# OnOnfre_DevBoard.net
KiCad netlist of a schematic drawn in EAGLE
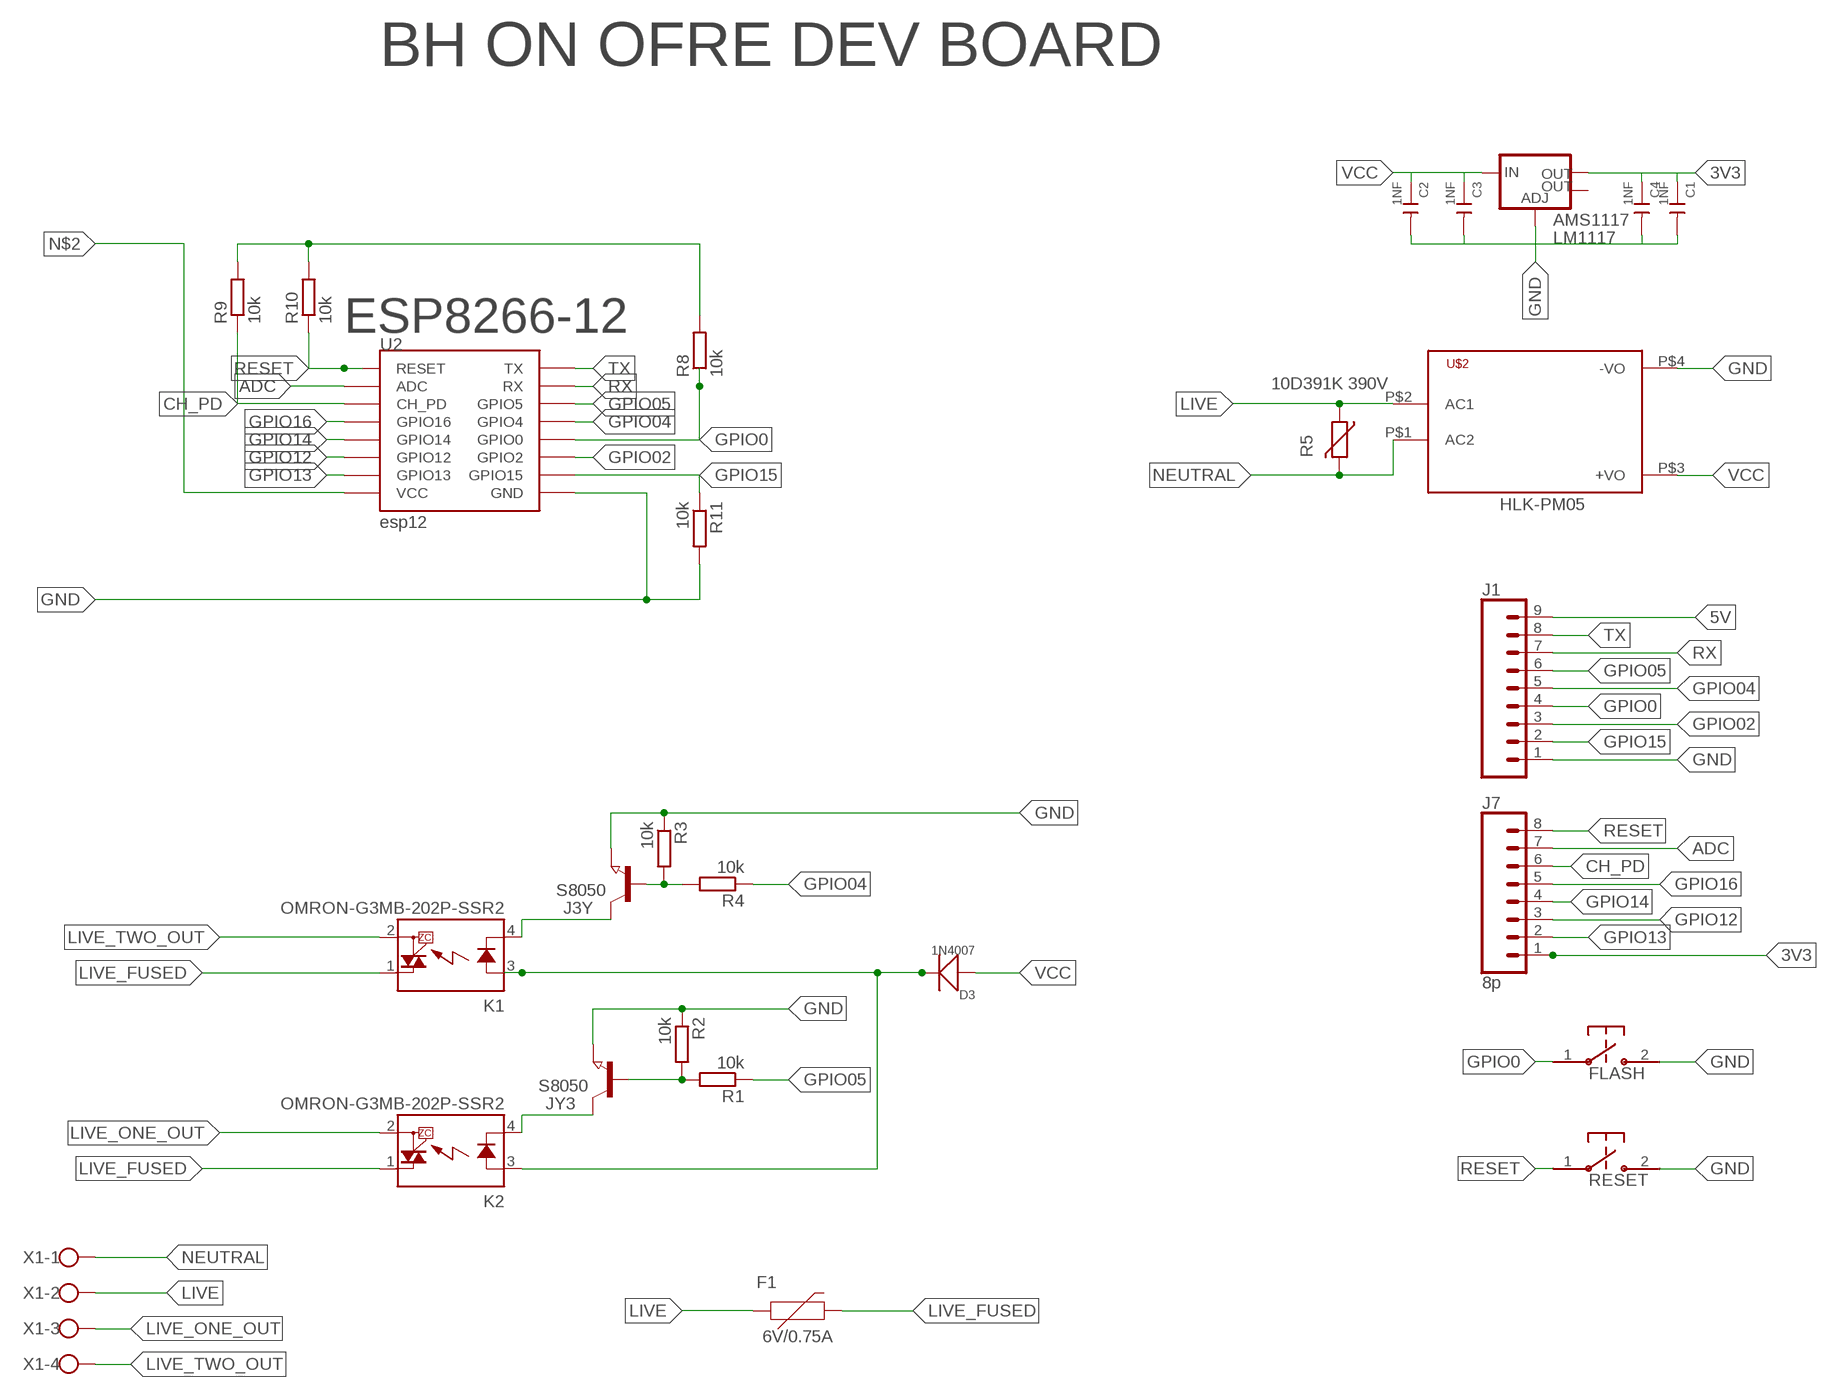
[diagram p0: schematic, sheet 1]

(export (version "E")
  (design (tool "Eeschema 10.0.6"))
  (components
    (comp (ref "AMS1117")
      (value "LM1117")
      (footprint "eagle-import:SOT223")
      (libsource (lib "eagle-import") (part "V_REG_LM1117SOT223"))
    )
    (comp (ref "C1")
      (value "1NF")
      (footprint "eagle-import:C1206")
      (fields (field (name "MPN") "CC1206KKX7RCBB102"))
      (libsource (lib "eagle-import") (part "CERAMIC-1NF-1KV-10%-X7R?(1206)"))
    )
    (comp (ref "C2")
      (value "1NF")
      (footprint "eagle-import:C1206")
      (fields (field (name "MPN") "CC1206KKX7RCBB102"))
      (libsource (lib "eagle-import") (part "CERAMIC-1NF-1KV-10%-X7R?(1206)"))
    )
    (comp (ref "C3")
      (value "1NF")
      (footprint "eagle-import:C1206")
      (fields (field (name "MPN") "CC1206KKX7RCBB102"))
      (libsource (lib "eagle-import") (part "CERAMIC-1NF-1KV-10%-X7R?(1206)"))
    )
    (comp (ref "C4")
      (value "1NF")
      (footprint "eagle-import:C1206")
      (fields (field (name "MPN") "CC1206KKX7RCBB102"))
      (libsource (lib "eagle-import") (part "CERAMIC-1NF-1KV-10%-X7R?(1206)"))
    )
    (comp (ref "D3")
      (value "1N4007")
      (footprint "eagle-import:DO-214AC")
      (libsource (lib "eagle-import") (part "DIODE-GEN-PURPOSE-1KV-1A(DO-214AC)"))
    )
    (comp (ref "F1")
      (value "6V/0.75A")
      (footprint "eagle-import:1206")
      (libsource (lib "eagle-import") (part "PPTC_THREE-QUARTER-AMP"))
    )
    (comp (ref "FLASH")
      (value "B3U-1000P-2P-SMD")
      (footprint "eagle-import:B3U-1000P")
      (fields (field (name "MANUFACTURER") "Omron") (field (name "MPN") "B3U-1000P"))
      (libsource (lib "eagle-import") (part "B3U-1000P"))
    )
    (comp (ref "J1")
      (value "CONN_09")
      (footprint "eagle-import:1X09")
      (libsource (lib "eagle-import") (part "CONN_09"))
    )
    (comp (ref "J3Y")
      (value "S8050")
      (footprint "eagle-import:SOT23")
      (libsource (lib "eagle-import") (part "NPN-TRANSISTOR_SOT23"))
    )
    (comp (ref "J7")
      (value "8p")
      (footprint "eagle-import:1X08")
      (libsource (lib "eagle-import") (part "CONN_08{dblquote}"))
    )
    (comp (ref "JY3")
      (value "S8050")
      (footprint "eagle-import:SOT23")
      (libsource (lib "eagle-import") (part "NPN-TRANSISTOR_SOT23"))
    )
    (comp (ref "K1")
      (value "OMRON-G3MB-202P-SSR2")
      (footprint "eagle-import:OMRON-G3MB-202P-SSR")
      (fields (field (name "MPN") "S202S02F"))
      (libsource (lib "eagle-import") (part "OMRON-G3MB-202P-SSR2"))
    )
    (comp (ref "K2")
      (value "OMRON-G3MB-202P-SSR2")
      (footprint "eagle-import:OMRON-G3MB-202P-SSR")
      (fields (field (name "MPN") "S202S02F"))
      (libsource (lib "eagle-import") (part "OMRON-G3MB-202P-SSR2"))
    )
    (comp (ref "R1")
      (value "10k")
      (footprint "eagle-import:R0603")
      (libsource (lib "eagle-import") (part "R-EU_R0603"))
    )
    (comp (ref "R2")
      (value "10k")
      (footprint "eagle-import:R0603")
      (libsource (lib "eagle-import") (part "R-EU_R0603"))
    )
    (comp (ref "R3")
      (value "10k")
      (footprint "eagle-import:R0603")
      (libsource (lib "eagle-import") (part "R-EU_R0603"))
    )
    (comp (ref "R4")
      (value "10k")
      (footprint "eagle-import:R0603")
      (libsource (lib "eagle-import") (part "R-EU_R0603"))
    )
    (comp (ref "R5")
      (value "10D391K 390V")
      (footprint "eagle-import:S07K230")
      (libsource (lib "eagle-import") (part "VARISTORS07K230"))
    )
    (comp (ref "R8")
      (value "10k")
      (footprint "eagle-import:R0603")
      (libsource (lib "eagle-import") (part "R-EU_R0603"))
    )
    (comp (ref "R9")
      (value "10k")
      (footprint "eagle-import:R0603")
      (libsource (lib "eagle-import") (part "R-EU_R0603"))
    )
    (comp (ref "R10")
      (value "10k")
      (footprint "eagle-import:R0603")
      (libsource (lib "eagle-import") (part "R-EU_R0603"))
    )
    (comp (ref "R11")
      (value "10k")
      (footprint "eagle-import:R0603")
      (libsource (lib "eagle-import") (part "R-EU_R0603"))
    )
    (comp (ref "RESET")
      (value "B3U-1000P-2P-SMD")
      (footprint "eagle-import:B3U-1000P")
      (fields (field (name "MANUFACTURER") "Omron") (field (name "MPN") "B3U-1000P"))
      (libsource (lib "eagle-import") (part "B3U-1000P"))
    )
    (comp (ref "U$2")
      (value "HKLPM01")
      (footprint "eagle-import:HKLPM01")
      (libsource (lib "eagle-import") (part "HKLPM01"))
    )
    (comp (ref "U2")
      (value "esp12")
      (footprint "eagle-import:ESP12-SMD")
      (libsource (lib "eagle-import") (part "ESP12SMD"))
    )
    (comp (ref "X1")
      (value "W237-4")
      (footprint "eagle-import:W237-4")
      (libsource (lib "eagle-import") (part "W237-4"))
    )
  )
  (nets
    (net (code "1") (name "3V3") (class "Default")
      (node (ref "AMS1117") (pin "2") (pinfunction "OUT_2") (pintype "output"))
      (node (ref "C1") (pin "1") (pinfunction "1_1") (pintype "passive"))
      (node (ref "C4") (pin "1") (pinfunction "1_1") (pintype "passive"))
      (node (ref "J7") (pin "1") (pinfunction "1_1") (pintype "passive"))
      (node (ref "R10") (pin "2") (pinfunction "2_2") (pintype "passive"))
      (node (ref "R8") (pin "2") (pinfunction "2_2") (pintype "passive"))
      (node (ref "R9") (pin "2") (pinfunction "2_2") (pintype "passive"))
    )
    (net (code "2") (name "5V") (class "Default")
      (node (ref "D3") (pin "2") (pinfunction "-_2") (pintype "passive"))
      (node (ref "J1") (pin "9") (pinfunction "9_9") (pintype "passive"))
      (node (ref "K1") (pin "3") (pinfunction "A_3") (pintype "passive"))
      (node (ref "K2") (pin "3") (pinfunction "A_3") (pintype "passive"))
    )
    (net (code "3") (name "ADC") (class "Default")
      (node (ref "J7") (pin "7") (pinfunction "7_7") (pintype "passive"))
      (node (ref "U2") (pin "ADC") (pinfunction "ADC_ADC") (pintype "bidirectional"))
    )
    (net (code "4") (name "CH_PD") (class "Default")
      (node (ref "J7") (pin "6") (pinfunction "6_6") (pintype "passive"))
      (node (ref "R9") (pin "1") (pinfunction "1_1") (pintype "passive"))
      (node (ref "U2") (pin "CH_PD") (pinfunction "CH_PD_CH_PD") (pintype "bidirectional"))
    )
    (net (code "5") (name "GND") (class "Default")
      (node (ref "AMS1117") (pin "1") (pinfunction "ADJ_1") (pintype "input"))
      (node (ref "C1") (pin "2") (pinfunction "2_2") (pintype "passive"))
      (node (ref "C2") (pin "2") (pinfunction "2_2") (pintype "passive"))
      (node (ref "C3") (pin "2") (pinfunction "2_2") (pintype "passive"))
      (node (ref "C4") (pin "2") (pinfunction "2_2") (pintype "passive"))
      (node (ref "FLASH") (pin "2") (pinfunction "P$2_2") (pintype "passive"))
      (node (ref "J1") (pin "1") (pinfunction "1_1") (pintype "passive"))
      (node (ref "J3Y") (pin "2") (pinfunction "E_2") (pintype "passive"))
      (node (ref "JY3") (pin "2") (pinfunction "E_2") (pintype "passive"))
      (node (ref "R11") (pin "2") (pinfunction "2_2") (pintype "passive"))
      (node (ref "R2") (pin "1") (pinfunction "1_1") (pintype "passive"))
      (node (ref "R3") (pin "1") (pinfunction "1_1") (pintype "passive"))
      (node (ref "RESET") (pin "2") (pinfunction "P$2_2") (pintype "passive"))
      (node (ref "U$2") (pin "P$4") (pinfunction "-VO_P$4") (pintype "bidirectional"))
      (node (ref "U2") (pin "GND") (pinfunction "GND_GND") (pintype "bidirectional"))
    )
    (net (code "6") (name "GPIO0") (class "Default")
      (node (ref "FLASH") (pin "1") (pinfunction "P$1_1") (pintype "passive"))
      (node (ref "J1") (pin "4") (pinfunction "4_4") (pintype "passive"))
      (node (ref "R8") (pin "1") (pinfunction "1_1") (pintype "passive"))
      (node (ref "U2") (pin "GPIO0") (pinfunction "GPIO0_GPIO0") (pintype "bidirectional"))
    )
    (net (code "7") (name "GPIO02") (class "Default")
      (node (ref "J1") (pin "3") (pinfunction "3_3") (pintype "passive"))
      (node (ref "U2") (pin "GPIO2") (pinfunction "GPIO2_GPIO2") (pintype "bidirectional"))
    )
    (net (code "8") (name "GPIO04") (class "Default")
      (node (ref "J1") (pin "5") (pinfunction "5_5") (pintype "passive"))
      (node (ref "R4") (pin "1") (pinfunction "1_1") (pintype "passive"))
      (node (ref "U2") (pin "GPIO4") (pinfunction "GPIO4_GPIO4") (pintype "bidirectional"))
    )
    (net (code "9") (name "GPIO05") (class "Default")
      (node (ref "J1") (pin "6") (pinfunction "6_6") (pintype "passive"))
      (node (ref "R1") (pin "1") (pinfunction "1_1") (pintype "passive"))
      (node (ref "U2") (pin "GPIO5") (pinfunction "GPIO5_GPIO5") (pintype "bidirectional"))
    )
    (net (code "10") (name "GPIO12") (class "Default")
      (node (ref "J7") (pin "3") (pinfunction "3_3") (pintype "passive"))
      (node (ref "U2") (pin "GPIO12") (pinfunction "GPIO12_GPIO12") (pintype "bidirectional"))
    )
    (net (code "11") (name "GPIO13") (class "Default")
      (node (ref "J7") (pin "2") (pinfunction "2_2") (pintype "passive"))
      (node (ref "U2") (pin "GPIO13") (pinfunction "GPIO13_GPIO13") (pintype "bidirectional"))
    )
    (net (code "12") (name "GPIO14") (class "Default")
      (node (ref "J7") (pin "4") (pinfunction "4_4") (pintype "passive"))
      (node (ref "U2") (pin "GPIO14") (pinfunction "GPIO14_GPIO14") (pintype "bidirectional"))
    )
    (net (code "13") (name "GPIO15") (class "Default")
      (node (ref "J1") (pin "2") (pinfunction "2_2") (pintype "passive"))
      (node (ref "R11") (pin "1") (pinfunction "1_1") (pintype "passive"))
      (node (ref "U2") (pin "GPIO15") (pinfunction "GPIO15_GPIO15") (pintype "bidirectional"))
    )
    (net (code "14") (name "GPIO16") (class "Default")
      (node (ref "J7") (pin "5") (pinfunction "5_5") (pintype "passive"))
      (node (ref "U2") (pin "GPIO16") (pinfunction "GPIO16_GPIO16") (pintype "bidirectional"))
    )
    (net (code "15") (name "LIVE") (class "Default")
      (node (ref "F1") (pin "1") (pinfunction "1_1") (pintype "bidirectional"))
      (node (ref "R5") (pin "1") (pinfunction "1_1") (pintype "passive"))
      (node (ref "U$2") (pin "P$2") (pinfunction "AC1_P$2") (pintype "bidirectional"))
      (node (ref "X1") (pin "2") (pinfunction "KL_2") (pintype "passive"))
    )
    (net (code "16") (name "LIVE_FUSED") (class "Default")
      (node (ref "F1") (pin "2") (pinfunction "2_2") (pintype "bidirectional"))
      (node (ref "K1") (pin "1") (pinfunction "DS1_1") (pintype "passive"))
      (node (ref "K2") (pin "1") (pinfunction "DS1_1") (pintype "passive"))
    )
    (net (code "17") (name "LIVE_ONE_OUT") (class "Default")
      (node (ref "K2") (pin "2") (pinfunction "DS2_2") (pintype "passive"))
      (node (ref "X1") (pin "3") (pinfunction "KL_3") (pintype "passive"))
    )
    (net (code "18") (name "LIVE_TWO_OUT") (class "Default")
      (node (ref "K1") (pin "2") (pinfunction "DS2_2") (pintype "passive"))
      (node (ref "X1") (pin "4") (pinfunction "KL_4") (pintype "passive"))
    )
    (net (code "19") (name "N$2") (class "Default")
      (node (ref "U2") (pin "VCC") (pinfunction "VCC_VCC") (pintype "bidirectional"))
    )
    (net (code "20") (name "NEUTRAL") (class "Default")
      (node (ref "R5") (pin "2") (pinfunction "2_2") (pintype "passive"))
      (node (ref "U$2") (pin "P$1") (pinfunction "AC2_P$1") (pintype "bidirectional"))
      (node (ref "X1") (pin "1") (pinfunction "KL_1") (pintype "passive"))
    )
    (net (code "21") (name "Net-(J3Y-B)") (class "Default")
      (node (ref "J3Y") (pin "1") (pinfunction "B_1") (pintype "passive"))
      (node (ref "R3") (pin "2") (pinfunction "2_2") (pintype "passive"))
      (node (ref "R4") (pin "2") (pinfunction "2_2") (pintype "passive"))
    )
    (net (code "22") (name "Net-(J3Y-C)") (class "Default")
      (node (ref "J3Y") (pin "3") (pinfunction "C_3") (pintype "passive"))
      (node (ref "K1") (pin "4") (pinfunction "K_4") (pintype "passive"))
    )
    (net (code "23") (name "Net-(JY3-B)") (class "Default")
      (node (ref "JY3") (pin "1") (pinfunction "B_1") (pintype "passive"))
      (node (ref "R1") (pin "2") (pinfunction "2_2") (pintype "passive"))
      (node (ref "R2") (pin "2") (pinfunction "2_2") (pintype "passive"))
    )
    (net (code "24") (name "Net-(JY3-C)") (class "Default")
      (node (ref "JY3") (pin "3") (pinfunction "C_3") (pintype "passive"))
      (node (ref "K2") (pin "4") (pinfunction "K_4") (pintype "passive"))
    )
    (net (code "25") (name "RESET") (class "Default")
      (node (ref "J7") (pin "8") (pinfunction "8_8") (pintype "passive"))
      (node (ref "R10") (pin "1") (pinfunction "1_1") (pintype "passive"))
      (node (ref "RESET") (pin "1") (pinfunction "P$1_1") (pintype "passive"))
      (node (ref "U2") (pin "RESET") (pinfunction "RESET_RESET") (pintype "bidirectional"))
    )
    (net (code "26") (name "RX") (class "Default")
      (node (ref "J1") (pin "7") (pinfunction "7_7") (pintype "passive"))
      (node (ref "U2") (pin "RXD0") (pinfunction "RX_RXD0") (pintype "bidirectional"))
    )
    (net (code "27") (name "TX") (class "Default")
      (node (ref "J1") (pin "8") (pinfunction "8_8") (pintype "passive"))
      (node (ref "U2") (pin "TXD0") (pinfunction "TX_TXD0") (pintype "bidirectional"))
    )
    (net (code "28") (name "VCC") (class "Default")
      (node (ref "AMS1117") (pin "3") (pinfunction "IN_3") (pintype "input"))
      (node (ref "C2") (pin "1") (pinfunction "1_1") (pintype "passive"))
      (node (ref "C3") (pin "1") (pinfunction "1_1") (pintype "passive"))
      (node (ref "D3") (pin "1") (pinfunction "+_1") (pintype "passive"))
      (node (ref "U$2") (pin "P$3") (pinfunction "+VO_P$3") (pintype "bidirectional"))
    )
    (net (code "29") (name "unconnected-(AMS1117-OUT-Pad4)") (class "Default")
      (node (ref "AMS1117") (pin "4") (pinfunction "OUT_4") (pintype "output"))
    )
  )
)
